# Rp2040.net
KiCad netlist of a schematic drawn in Altium Designer
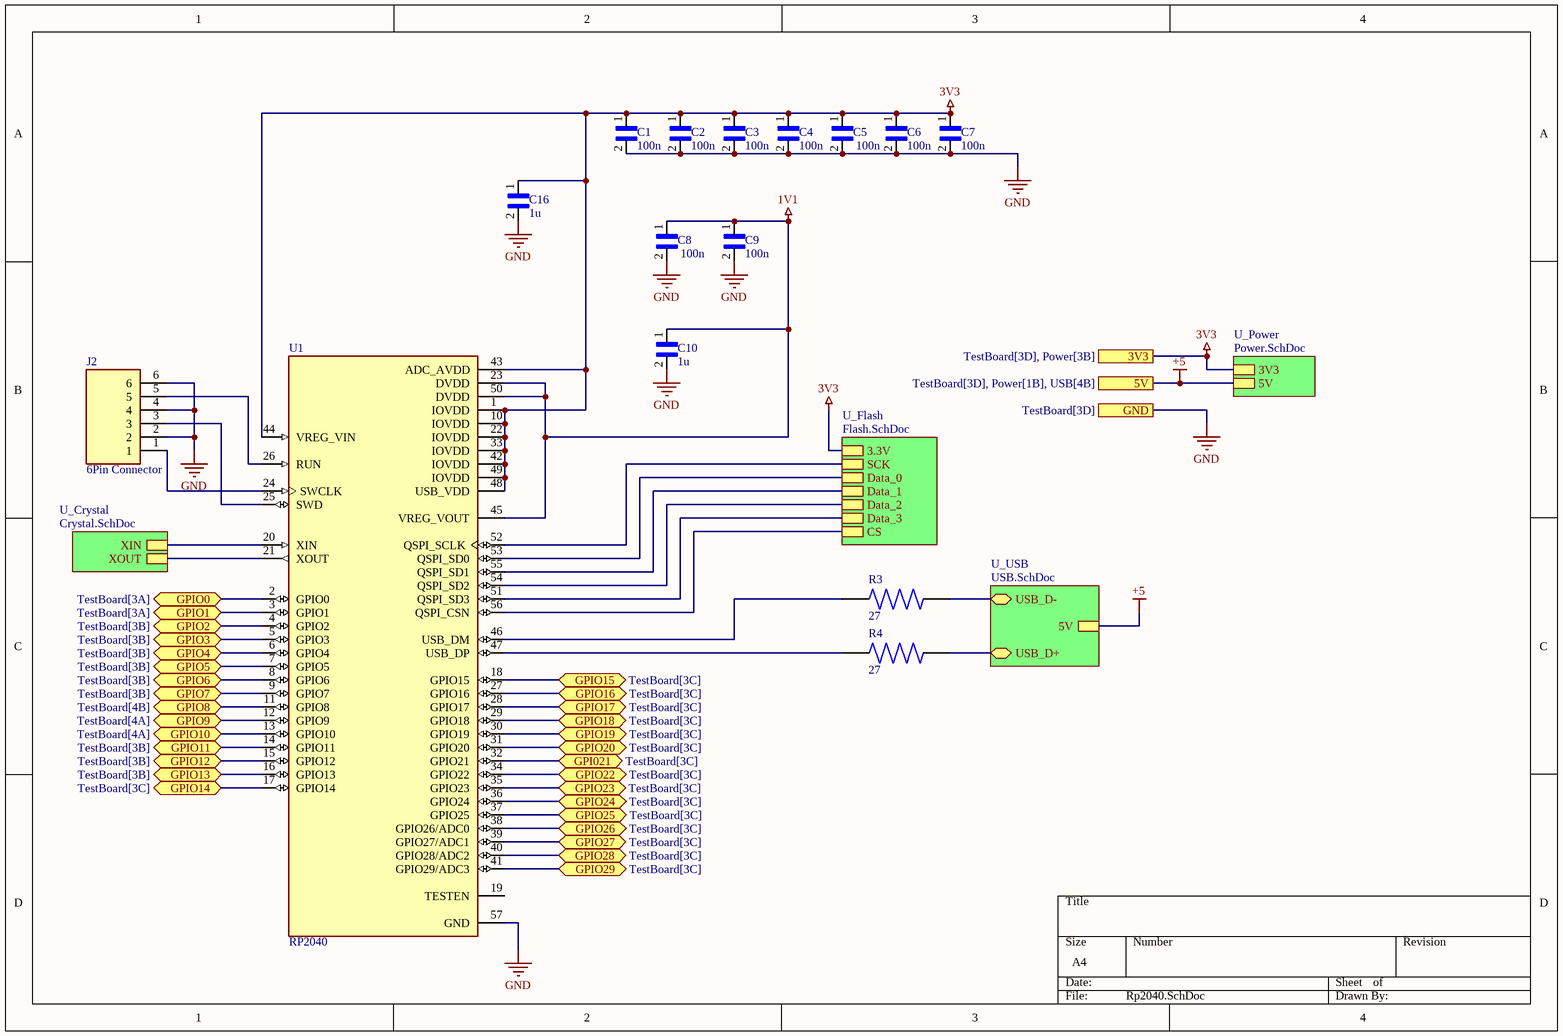
[diagram p0: Rp2040.SchDoc]

(export (version "E")
  (design (tool "Eeschema 10.0.6"))
  (components
    (comp (ref "C1")
      (value "100n")
      (footprint "SMD Capacator")
      (libsource (lib "Basic") (part "SMD Capacator"))
    )
    (comp (ref "C2")
      (value "100n")
      (footprint "SMD Capacator")
      (libsource (lib "Basic") (part "SMD Capacator"))
    )
    (comp (ref "C3")
      (value "100n")
      (footprint "SMD Capacator")
      (libsource (lib "Basic") (part "SMD Capacator"))
    )
    (comp (ref "C4")
      (value "100n")
      (footprint "SMD Capacator")
      (libsource (lib "Basic") (part "SMD Capacator"))
    )
    (comp (ref "C5")
      (value "100n")
      (footprint "SMD Capacator")
      (libsource (lib "Basic") (part "SMD Capacator"))
    )
    (comp (ref "C6")
      (value "100n")
      (footprint "SMD Capacator")
      (libsource (lib "Basic") (part "SMD Capacator"))
    )
    (comp (ref "C7")
      (value "100n")
      (footprint "SMD Capacator")
      (libsource (lib "Basic") (part "SMD Capacator"))
    )
    (comp (ref "C8")
      (value "100n")
      (footprint "SMD Capacator")
      (libsource (lib "Basic") (part "SMD Capacator"))
    )
    (comp (ref "C9")
      (value "100n")
      (footprint "SMD Capacator")
      (libsource (lib "Basic") (part "SMD Capacator"))
    )
    (comp (ref "C10")
      (value "1u")
      (footprint "SMD Capacator")
      (libsource (lib "Basic") (part "SMD Capacator"))
    )
    (comp (ref "C16")
      (value "1u")
      (footprint "SMD Capacator")
      (libsource (lib "Basic") (part "SMD Capacator"))
    )
    (comp (ref "J2")
      (value "6Pin Connector")
      (footprint "6Pin Connector")
      (libsource (lib "Basic") (part "6Pin Connector"))
    )
    (comp (ref "R3") (value "27") (footprint "SMD Resistor") (libsource (lib "Basic") (part "SMD Resistor")))
    (comp (ref "R4") (value "27") (footprint "SMD Resistor") (libsource (lib "Basic") (part "SMD Resistor")))
    (comp (ref "U1") (value "RP2040") (footprint "RP2040") (libsource (lib "Basic") (part "RP2040")))
  )
  (nets
    (net (code "2") (name "/CS") (class "Default")
      (node (ref "U1") (pin "56") (pinfunction "QSPI_CSN_56") (pintype "bidirectional"))
    )
    (net (code "3") (name "/Data_0") (class "Default")
      (node (ref "U1") (pin "53") (pinfunction "QSPI_SD0_53") (pintype "bidirectional"))
    )
    (net (code "4") (name "/Data_1") (class "Default")
      (node (ref "U1") (pin "55") (pinfunction "QSPI_SD1_55") (pintype "bidirectional"))
    )
    (net (code "5") (name "/Data_2") (class "Default")
      (node (ref "U1") (pin "54") (pinfunction "QSPI_SD2_54") (pintype "bidirectional"))
    )
    (net (code "6") (name "/Data_3") (class "Default")
      (node (ref "U1") (pin "51") (pinfunction "QSPI_SD3_51") (pintype "bidirectional"))
    )
    (net (code "7") (name "/GPI021") (class "Default")
      (node (ref "U1") (pin "32") (pinfunction "GPIO21_32") (pintype "bidirectional"))
    )
    (net (code "8") (name "/GPIO0") (class "Default")
      (node (ref "U1") (pin "2") (pinfunction "GPIO0_2") (pintype "bidirectional"))
    )
    (net (code "9") (name "/GPIO1") (class "Default")
      (node (ref "U1") (pin "3") (pinfunction "GPIO1_3") (pintype "bidirectional"))
    )
    (net (code "10") (name "/GPIO2") (class "Default")
      (node (ref "U1") (pin "4") (pinfunction "GPIO2_4") (pintype "bidirectional"))
    )
    (net (code "11") (name "/GPIO3") (class "Default")
      (node (ref "U1") (pin "5") (pinfunction "GPIO3_5") (pintype "bidirectional"))
    )
    (net (code "12") (name "/GPIO4") (class "Default")
      (node (ref "U1") (pin "6") (pinfunction "GPIO4_6") (pintype "bidirectional"))
    )
    (net (code "13") (name "/GPIO5") (class "Default")
      (node (ref "U1") (pin "7") (pinfunction "GPIO5_7") (pintype "bidirectional"))
    )
    (net (code "14") (name "/GPIO6") (class "Default")
      (node (ref "U1") (pin "8") (pinfunction "GPIO6_8") (pintype "bidirectional"))
    )
    (net (code "15") (name "/GPIO7") (class "Default")
      (node (ref "U1") (pin "9") (pinfunction "GPIO7_9") (pintype "bidirectional"))
    )
    (net (code "16") (name "/GPIO8") (class "Default")
      (node (ref "U1") (pin "11") (pinfunction "GPIO8_11") (pintype "bidirectional"))
    )
    (net (code "17") (name "/GPIO9") (class "Default")
      (node (ref "U1") (pin "12") (pinfunction "GPIO9_12") (pintype "bidirectional"))
    )
    (net (code "18") (name "/GPIO10") (class "Default")
      (node (ref "U1") (pin "13") (pinfunction "GPIO10_13") (pintype "bidirectional"))
    )
    (net (code "19") (name "/GPIO11") (class "Default")
      (node (ref "U1") (pin "14") (pinfunction "GPIO11_14") (pintype "bidirectional"))
    )
    (net (code "20") (name "/GPIO12") (class "Default")
      (node (ref "U1") (pin "15") (pinfunction "GPIO12_15") (pintype "bidirectional"))
    )
    (net (code "21") (name "/GPIO13") (class "Default")
      (node (ref "U1") (pin "16") (pinfunction "GPIO13_16") (pintype "bidirectional"))
    )
    (net (code "22") (name "/GPIO14") (class "Default")
      (node (ref "U1") (pin "17") (pinfunction "GPIO14_17") (pintype "bidirectional"))
    )
    (net (code "23") (name "/GPIO15") (class "Default")
      (node (ref "U1") (pin "18") (pinfunction "GPIO15_18") (pintype "bidirectional"))
    )
    (net (code "24") (name "/GPIO16") (class "Default")
      (node (ref "U1") (pin "27") (pinfunction "GPIO16_27") (pintype "bidirectional"))
    )
    (net (code "25") (name "/GPIO17") (class "Default")
      (node (ref "U1") (pin "28") (pinfunction "GPIO17_28") (pintype "bidirectional"))
    )
    (net (code "26") (name "/GPIO18") (class "Default")
      (node (ref "U1") (pin "29") (pinfunction "GPIO18_29") (pintype "bidirectional"))
    )
    (net (code "27") (name "/GPIO19") (class "Default")
      (node (ref "U1") (pin "30") (pinfunction "GPIO19_30") (pintype "bidirectional"))
    )
    (net (code "28") (name "/GPIO20") (class "Default")
      (node (ref "U1") (pin "31") (pinfunction "GPIO20_31") (pintype "bidirectional"))
    )
    (net (code "29") (name "/GPIO22") (class "Default")
      (node (ref "U1") (pin "34") (pinfunction "GPIO22_34") (pintype "bidirectional"))
    )
    (net (code "30") (name "/GPIO23") (class "Default")
      (node (ref "U1") (pin "35") (pinfunction "GPIO23_35") (pintype "bidirectional"))
    )
    (net (code "31") (name "/GPIO24") (class "Default")
      (node (ref "U1") (pin "36") (pinfunction "GPIO24_36") (pintype "bidirectional"))
    )
    (net (code "32") (name "/GPIO25") (class "Default")
      (node (ref "U1") (pin "37") (pinfunction "GPIO25_37") (pintype "bidirectional"))
    )
    (net (code "33") (name "/GPIO26") (class "Default")
      (node (ref "U1") (pin "38") (pinfunction "GPIO26/ADC0_38") (pintype "bidirectional"))
    )
    (net (code "34") (name "/GPIO27") (class "Default")
      (node (ref "U1") (pin "39") (pinfunction "GPIO27/ADC1_39") (pintype "bidirectional"))
    )
    (net (code "35") (name "/GPIO28") (class "Default")
      (node (ref "U1") (pin "40") (pinfunction "GPIO28/ADC2_40") (pintype "bidirectional"))
    )
    (net (code "36") (name "/GPIO29") (class "Default")
      (node (ref "U1") (pin "41") (pinfunction "GPIO29/ADC3_41") (pintype "bidirectional"))
    )
    (net (code "37") (name "/SCK") (class "Default")
      (node (ref "U1") (pin "52") (pinfunction "QSPI_SCLK_52") (pintype "bidirectional"))
    )
    (net (code "38") (name "/USB_D+") (class "Default")
      (node (ref "R4") (pin "2") (pinfunction "2_2") (pintype "passive"))
    )
    (net (code "39") (name "/USB_D-") (class "Default")
      (node (ref "R3") (pin "2") (pinfunction "2_2") (pintype "passive"))
    )
    (net (code "40") (name "/XIN") (class "Default")
      (node (ref "U1") (pin "20") (pinfunction "XIN_20") (pintype "input"))
    )
    (net (code "41") (name "/XOUT") (class "Default")
      (node (ref "U1") (pin "21") (pinfunction "XOUT_21") (pintype "output"))
    )
    (net (code "42") (name "1V1") (class "Default")
      (node (ref "C10") (pin "1") (pinfunction "1_1") (pintype "passive"))
      (node (ref "C8") (pin "1") (pinfunction "1_1") (pintype "passive"))
      (node (ref "C9") (pin "1") (pinfunction "1_1") (pintype "passive"))
      (node (ref "U1") (pin "23") (pinfunction "DVDD_23") (pintype "power_in"))
      (node (ref "U1") (pin "45") (pinfunction "VREG_VOUT_45") (pintype "power_in"))
      (node (ref "U1") (pin "50") (pinfunction "DVDD_50") (pintype "power_in"))
    )
    (net (code "43") (name "3V3") (class "Default")
      (node (ref "C1") (pin "1") (pinfunction "1_1") (pintype "passive"))
      (node (ref "C16") (pin "1") (pinfunction "1_1") (pintype "passive"))
      (node (ref "C2") (pin "1") (pinfunction "1_1") (pintype "passive"))
      (node (ref "C3") (pin "1") (pinfunction "1_1") (pintype "passive"))
      (node (ref "C4") (pin "1") (pinfunction "1_1") (pintype "passive"))
      (node (ref "C5") (pin "1") (pinfunction "1_1") (pintype "passive"))
      (node (ref "C6") (pin "1") (pinfunction "1_1") (pintype "passive"))
      (node (ref "C7") (pin "1") (pinfunction "1_1") (pintype "passive"))
      (node (ref "U1") (pin "1") (pinfunction "IOVDD_1") (pintype "power_in"))
      (node (ref "U1") (pin "10") (pinfunction "IOVDD_10") (pintype "power_in"))
      (node (ref "U1") (pin "22") (pinfunction "IOVDD_22") (pintype "power_in"))
      (node (ref "U1") (pin "33") (pinfunction "IOVDD_33") (pintype "power_in"))
      (node (ref "U1") (pin "42") (pinfunction "IOVDD_42") (pintype "power_in"))
      (node (ref "U1") (pin "43") (pinfunction "ADC_AVDD_43") (pintype "power_in"))
      (node (ref "U1") (pin "44") (pinfunction "VREG_VIN_44") (pintype "input"))
      (node (ref "U1") (pin "48") (pinfunction "USB_VDD_48") (pintype "power_in"))
      (node (ref "U1") (pin "49") (pinfunction "IOVDD_49") (pintype "power_in"))
    )
    (net (code "44") (name "GND") (class "Default")
      (node (ref "C1") (pin "2") (pinfunction "2_2") (pintype "passive"))
      (node (ref "C10") (pin "2") (pinfunction "2_2") (pintype "passive"))
      (node (ref "C16") (pin "2") (pinfunction "2_2") (pintype "passive"))
      (node (ref "C2") (pin "2") (pinfunction "2_2") (pintype "passive"))
      (node (ref "C3") (pin "2") (pinfunction "2_2") (pintype "passive"))
      (node (ref "C4") (pin "2") (pinfunction "2_2") (pintype "passive"))
      (node (ref "C5") (pin "2") (pinfunction "2_2") (pintype "passive"))
      (node (ref "C6") (pin "2") (pinfunction "2_2") (pintype "passive"))
      (node (ref "C7") (pin "2") (pinfunction "2_2") (pintype "passive"))
      (node (ref "C8") (pin "2") (pinfunction "2_2") (pintype "passive"))
      (node (ref "C9") (pin "2") (pinfunction "2_2") (pintype "passive"))
      (node (ref "J2") (pin "2") (pinfunction "2_2") (pintype "passive"))
      (node (ref "J2") (pin "4") (pinfunction "4_4") (pintype "passive"))
      (node (ref "J2") (pin "6") (pinfunction "6_6") (pintype "passive"))
      (node (ref "U1") (pin "57") (pinfunction "GND_57") (pintype "power_in"))
    )
    (net (code "45") (name "Net-(U1-RUN)") (class "Default")
      (node (ref "J2") (pin "5") (pinfunction "5_5") (pintype "passive"))
      (node (ref "U1") (pin "26") (pinfunction "RUN_26") (pintype "input"))
    )
    (net (code "46") (name "Net-(U1-SWCLK)") (class "Default")
      (node (ref "J2") (pin "1") (pinfunction "1_1") (pintype "passive"))
      (node (ref "U1") (pin "24") (pinfunction "SWCLK_24") (pintype "input"))
    )
    (net (code "47") (name "Net-(U1-SWD)") (class "Default")
      (node (ref "J2") (pin "3") (pinfunction "3_3") (pintype "passive"))
      (node (ref "U1") (pin "25") (pinfunction "SWD_25") (pintype "bidirectional"))
    )
    (net (code "48") (name "Net-(U1-USB_DM)") (class "Default")
      (node (ref "R3") (pin "1") (pinfunction "1_1") (pintype "passive"))
      (node (ref "U1") (pin "46") (pinfunction "USB_DM_46") (pintype "bidirectional"))
    )
    (net (code "49") (name "Net-(U1-USB_DP)") (class "Default")
      (node (ref "R4") (pin "1") (pinfunction "1_1") (pintype "passive"))
      (node (ref "U1") (pin "47") (pinfunction "USB_DP_47") (pintype "bidirectional"))
    )
    (net (code "50") (name "unconnected-(U1-TESTEN-Pad19)") (class "Default")
      (node (ref "U1") (pin "19") (pinfunction "TESTEN_19") (pintype "passive"))
    )
  )
)
